# BM680.net
KiCad netlist of a schematic drawn in Altium Designer
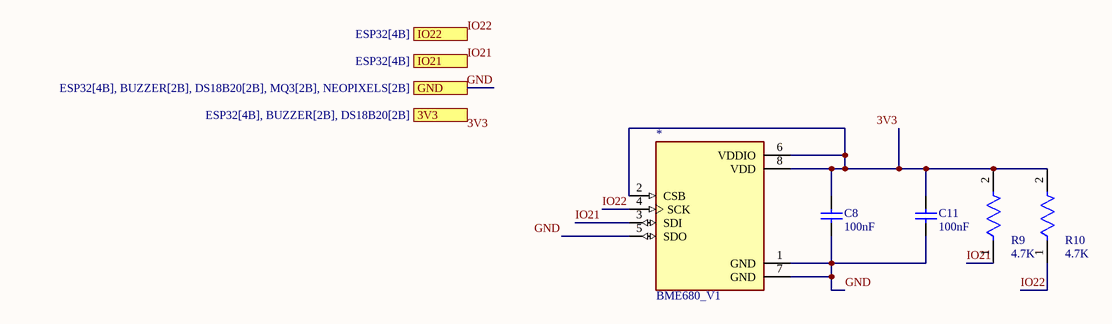
[diagram p0: BM680.SchDoc]

(export (version "E")
  (design (tool "Eeschema 10.0.6"))
  (components
    (comp (ref "*")
      (value "BME680_V1")
      (footprint "BME680")
      (libsource (lib "Isidro_Library") (part "BME680_V1"))
    )
    (comp (ref "C8")
      (value "100nF")
      (footprint "CAPC2013X140X50ML20T25")
      (description "10µF ±10% 16V Ceramic Capacitor X5R 0805 (2012 Metric)")
      (fields (field (name "PART NUMBER") "CL21A106KOQNNNG"))
      (libsource (lib "Altium Content Vault") (part "CAP"))
    )
    (comp (ref "C11")
      (value "100nF")
      (footprint "CAPC2013X140X50ML20T25")
      (description "10µF ±10% 16V Ceramic Capacitor X5R 0805 (2012 Metric)")
      (fields (field (name "PART NUMBER") "CL21A106KOQNNNG"))
      (libsource (lib "Altium Content Vault") (part "CAP"))
    )
    (comp (ref "R9")
      (value "4.7K")
      (footprint "FP-ERA6A-IPC_B")
      (description "RES 100K OHM 0.1% 1/8W 0805")
      (fields (field (name "TOLERANCE") "0.1%"))
      (libsource (lib "Altium Content Vault") (part "1029c3af85768c4190bb7ad29bc67b5"))
    )
    (comp (ref "R10")
      (value "4.7K")
      (footprint "FP-ERA6A-IPC_B")
      (description "RES 100K OHM 0.1% 1/8W 0805")
      (fields (field (name "TOLERANCE") "0.1%"))
      (libsource (lib "Altium Content Vault") (part "1029c3af85768c4190bb7ad29bc67b5"))
    )
  )
  (nets
    (net (code "1") (name "/3V3") (class "Default")
      (node (ref "*") (pin "2") (pinfunction "CSB_2") (pintype "input"))
      (node (ref "*") (pin "6") (pinfunction "VDDIO_6") (pintype "power_in"))
      (node (ref "*") (pin "8") (pinfunction "VDD_8") (pintype "power_in"))
      (node (ref "C11") (pin "2") (pinfunction "2_2") (pintype "passive"))
      (node (ref "C8") (pin "2") (pinfunction "2_2") (pintype "passive"))
      (node (ref "R10") (pin "2") (pinfunction "2_2") (pintype "passive"))
      (node (ref "R9") (pin "2") (pinfunction "2_2") (pintype "passive"))
    )
    (net (code "2") (name "/GND") (class "Default")
      (node (ref "*") (pin "1") (pinfunction "GND_1") (pintype "power_in"))
      (node (ref "*") (pin "5") (pinfunction "SDO_5") (pintype "bidirectional"))
      (node (ref "*") (pin "7") (pinfunction "GND_7") (pintype "power_in"))
      (node (ref "C11") (pin "1") (pinfunction "1_1") (pintype "passive"))
      (node (ref "C8") (pin "1") (pinfunction "1_1") (pintype "passive"))
    )
    (net (code "3") (name "/IO21") (class "Default")
      (node (ref "*") (pin "3") (pinfunction "SDI_3") (pintype "bidirectional"))
      (node (ref "R9") (pin "1") (pinfunction "1_1") (pintype "passive"))
    )
    (net (code "4") (name "/IO22") (class "Default")
      (node (ref "*") (pin "4") (pinfunction "SCK_4") (pintype "input"))
      (node (ref "R10") (pin "1") (pinfunction "1_1") (pintype "passive"))
    )
  )
)
